# LCD_PWR.net
KiCad netlist of a schematic drawn in Altium Designer
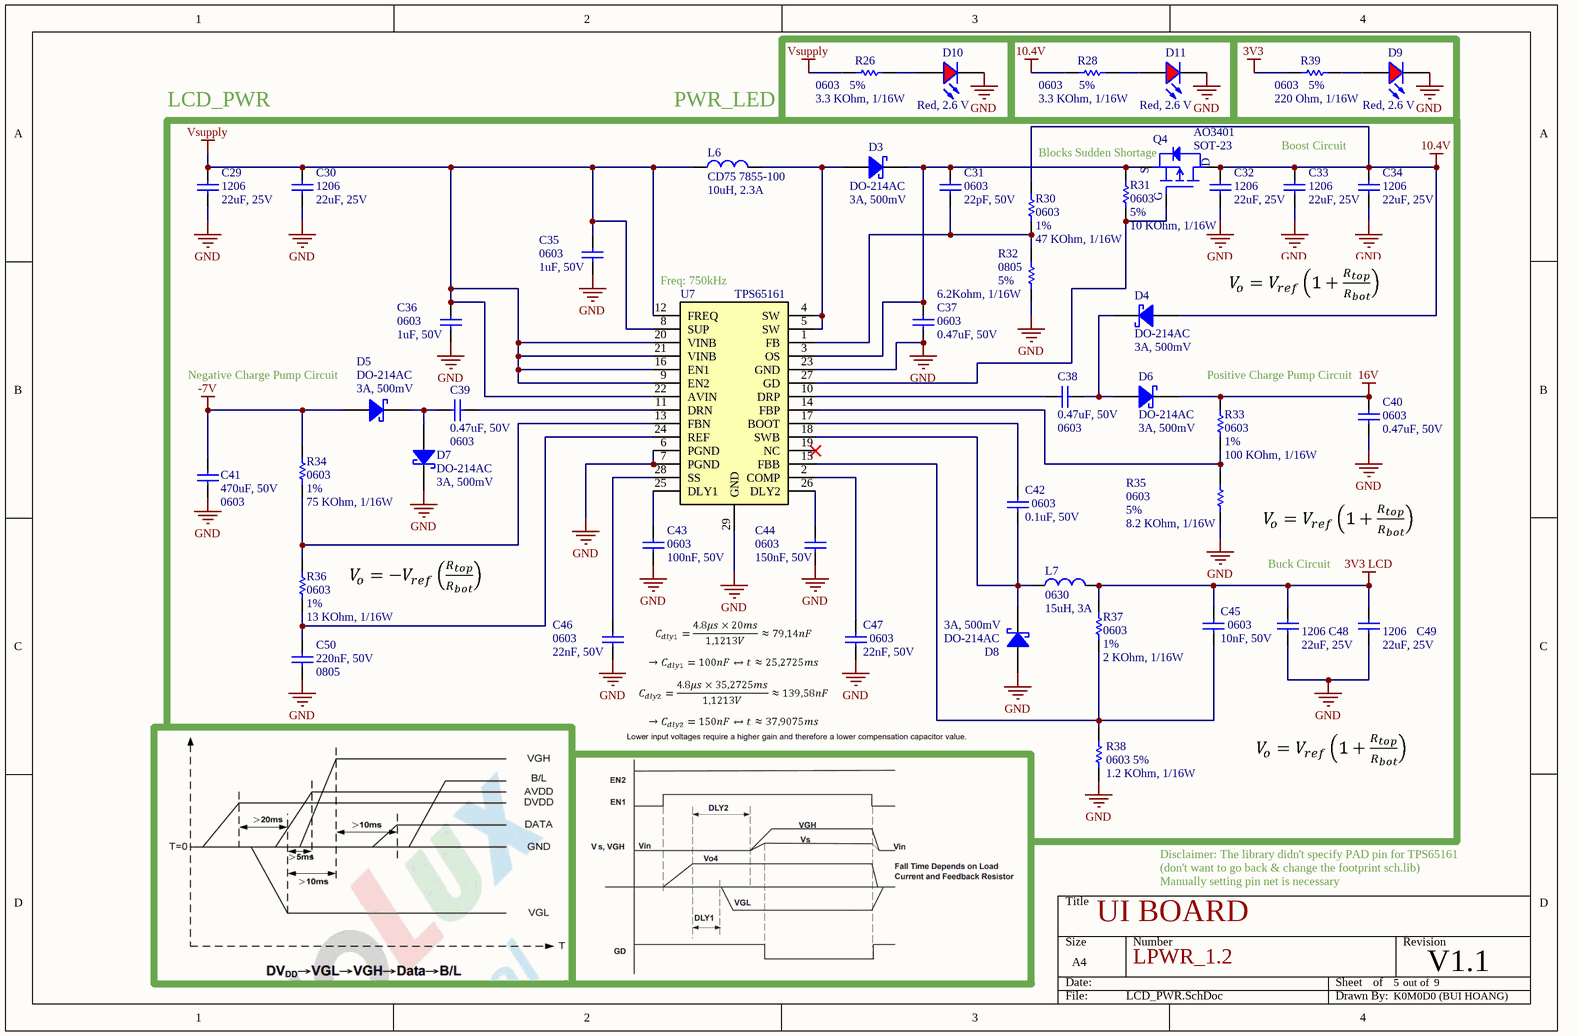
[diagram p0: LCD_PWR.SchDoc]

(export (version "E")
  (design (tool "Eeschema 10.0.6"))
  (components
    (comp (ref "C29")
      (value "22uF, 25V")
      (footprint "C_1206")
      (description "CAP_1206")
      (fields (field (name "PACKAGE") "1206"))
      (libsource (lib "DisplayLib") (part "CAP_1206"))
    )
    (comp (ref "C30")
      (value "22uF, 25V")
      (footprint "C_1206")
      (description "CAP_1206")
      (fields (field (name "PACKAGE") "1206"))
      (libsource (lib "DisplayLib") (part "CAP_1206"))
    )
    (comp (ref "C31")
      (value "22pF, 50V")
      (footprint "C_0603")
      (description "CAP_0603")
      (fields (field (name "PACKAGE") "0603"))
      (libsource (lib "DisplayLib") (part "CAP_0603"))
    )
    (comp (ref "C32")
      (value "22uF, 25V")
      (footprint "C_1206")
      (description "CAP_1206")
      (fields (field (name "PACKAGE") "1206"))
      (libsource (lib "DisplayLib") (part "CAP_1206"))
    )
    (comp (ref "C33")
      (value "22uF, 25V")
      (footprint "C_1206")
      (description "CAP_1206")
      (fields (field (name "PACKAGE") "1206"))
      (libsource (lib "DisplayLib") (part "CAP_1206"))
    )
    (comp (ref "C34")
      (value "22uF, 25V")
      (footprint "C_1206")
      (description "CAP_1206")
      (fields (field (name "PACKAGE") "1206"))
      (libsource (lib "DisplayLib") (part "CAP_1206"))
    )
    (comp (ref "C35")
      (value "1uF, 50V")
      (footprint "C_0603")
      (description "CAP_0603")
      (fields (field (name "PACKAGE") "0603"))
      (libsource (lib "DisplayLib") (part "CAP_0603"))
    )
    (comp (ref "C36")
      (value "1uF, 50V")
      (footprint "C_0603")
      (description "CAP_0603")
      (fields (field (name "PACKAGE") "0603"))
      (libsource (lib "DisplayLib") (part "CAP_0603"))
    )
    (comp (ref "C37")
      (value "0.47uF, 50V")
      (footprint "C_0603")
      (description "CAP_0603")
      (fields (field (name "PACKAGE") "0603"))
      (libsource (lib "DisplayLib") (part "CAP_0603"))
    )
    (comp (ref "C38")
      (value "0.47uF, 50V")
      (footprint "C_0603")
      (description "CAP_0603")
      (fields (field (name "PACKAGE") "0603"))
      (libsource (lib "DisplayLib") (part "CAP_0603"))
    )
    (comp (ref "C39")
      (value "0.47uF, 50V")
      (footprint "C_0603")
      (description "CAP_0603")
      (fields (field (name "PACKAGE") "0603"))
      (libsource (lib "DisplayLib") (part "CAP_0603"))
    )
    (comp (ref "C40")
      (value "0.47uF, 50V")
      (footprint "C_0603")
      (description "CAP_0603")
      (fields (field (name "PACKAGE") "0603"))
      (libsource (lib "DisplayLib") (part "CAP_0603"))
    )
    (comp (ref "C41")
      (value "470uF, 50V")
      (footprint "C_0603")
      (description "CAP_0603")
      (fields (field (name "PACKAGE") "0603"))
      (libsource (lib "DisplayLib") (part "CAP_0603"))
    )
    (comp (ref "C42")
      (value "0.1uF, 50V")
      (footprint "C_0603")
      (description "CAP_0603")
      (fields (field (name "PACKAGE") "0603"))
      (libsource (lib "DisplayLib") (part "CAP_0603"))
    )
    (comp (ref "C43")
      (value "100nF, 50V")
      (footprint "C_0603")
      (description "CAP_0603")
      (fields (field (name "PACKAGE") "0603"))
      (libsource (lib "DisplayLib") (part "CAP_0603"))
    )
    (comp (ref "C44")
      (value "150nF, 50V")
      (footprint "C_0603")
      (description "CAP_0603")
      (fields (field (name "PACKAGE") "0603"))
      (libsource (lib "DisplayLib") (part "CAP_0603"))
    )
    (comp (ref "C45")
      (value "10nF, 50V")
      (footprint "C_0603")
      (description "CAP_0603")
      (fields (field (name "PACKAGE") "0603"))
      (libsource (lib "DisplayLib") (part "CAP_0603"))
    )
    (comp (ref "C46")
      (value "22nF, 50V")
      (footprint "C_0603")
      (description "CAP_0603")
      (fields (field (name "PACKAGE") "0603"))
      (libsource (lib "DisplayLib") (part "CAP_0603"))
    )
    (comp (ref "C47")
      (value "22nF, 50V")
      (footprint "C_0603")
      (description "CAP_0603")
      (fields (field (name "PACKAGE") "0603"))
      (libsource (lib "DisplayLib") (part "CAP_0603"))
    )
    (comp (ref "C48")
      (value "22uF, 25V")
      (footprint "C_1206")
      (description "CAP_1206")
      (fields (field (name "PACKAGE") "1206"))
      (libsource (lib "DisplayLib") (part "CAP_1206"))
    )
    (comp (ref "C49")
      (value "22uF, 25V")
      (footprint "C_1206")
      (description "CAP_1206")
      (fields (field (name "PACKAGE") "1206"))
      (libsource (lib "DisplayLib") (part "CAP_1206"))
    )
    (comp (ref "C50")
      (value "220nF, 50V")
      (footprint "C_0805")
      (description "CAP_0805")
      (fields (field (name "PACKAGE") "0805"))
      (libsource (lib "DisplayLib") (part "CAP_0805"))
    )
    (comp (ref "D3")
      (value "3A, 500mV")
      (footprint "PKG_SMA (DO-214AC)")
      (description "SS34")
      (fields (field (name "PACKAGE") "DO-214AC"))
      (libsource (lib "DisplayLib") (part "SCHOTTKY"))
    )
    (comp (ref "D4")
      (value "3A, 500mV")
      (footprint "PKG_SMA (DO-214AC)")
      (description "SS34")
      (fields (field (name "PACKAGE") "DO-214AC"))
      (libsource (lib "DisplayLib") (part "SCHOTTKY"))
    )
    (comp (ref "D5")
      (value "3A, 500mV")
      (footprint "PKG_SMA (DO-214AC)")
      (description "SS34")
      (fields (field (name "PACKAGE") "DO-214AC"))
      (libsource (lib "DisplayLib") (part "SCHOTTKY"))
    )
    (comp (ref "D6")
      (value "3A, 500mV")
      (footprint "PKG_SMA (DO-214AC)")
      (description "SS34")
      (fields (field (name "PACKAGE") "DO-214AC"))
      (libsource (lib "DisplayLib") (part "SCHOTTKY"))
    )
    (comp (ref "D7")
      (value "3A, 500mV")
      (footprint "PKG_SMA (DO-214AC)")
      (description "SS34")
      (fields (field (name "PACKAGE") "DO-214AC"))
      (libsource (lib "DisplayLib") (part "SCHOTTKY"))
    )
    (comp (ref "D8")
      (value "3A, 500mV")
      (footprint "PKG_SMA (DO-214AC)")
      (description "SS34")
      (fields (field (name "PACKAGE") "DO-214AC"))
      (libsource (lib "DisplayLib") (part "SCHOTTKY"))
    )
    (comp (ref "D9")
      (value "Red, 2.6 V")
      (footprint "LED_1206")
      (description "Red LED")
      (libsource (lib "DisplayLib") (part "RED"))
    )
    (comp (ref "D10")
      (value "Red, 2.6 V")
      (footprint "LED_1206")
      (description "Red LED")
      (libsource (lib "DisplayLib") (part "RED"))
    )
    (comp (ref "D11")
      (value "Red, 2.6 V")
      (footprint "LED_1206")
      (description "Red LED")
      (libsource (lib "DisplayLib") (part "RED"))
    )
    (comp (ref "L6")
      (value "10uH, 2.3A")
      (footprint "COIL_CDRH")
      (description "IN_CD104_100")
      (fields (field (name "PACKAGE") "CD75 7855-100"))
      (libsource (lib "DisplayLib") (part "IN_CD104_100"))
    )
    (comp (ref "L7")
      (value "15uH, 3A")
      (footprint "COIL_74")
      (description "IN_0630")
      (fields (field (name "PACKAGE") "0630"))
      (libsource (lib "DisplayLib") (part "IN_0630"))
    )
    (comp (ref "Q4")
      (value "AO3401")
      (footprint "PKG_SOT-23")
      (description "P-Channel 30 V 4A (Ta) 1.4W (Ta) Surface Mount SOT-23-3")
      (fields (field (name "PACKAGE") "SOT-23"))
      (libsource (lib "DisplayLib") (part "AO3401"))
    )
    (comp (ref "R26")
      (value "3.3 KOhm, 1/16W")
      (footprint "R_0603")
      (description "RES_0603")
      (fields (field (name "PACKAGE") "0603") (field (name "ACC") "5%"))
      (libsource (lib "DisplayLib") (part "RES_0603"))
    )
    (comp (ref "R28")
      (value "3.3 KOhm, 1/16W")
      (footprint "R_0603")
      (description "RES_0603")
      (fields (field (name "PACKAGE") "0603") (field (name "ACC") "5%"))
      (libsource (lib "DisplayLib") (part "RES_0603"))
    )
    (comp (ref "R30")
      (value "47 KOhm, 1/16W")
      (footprint "R_0603")
      (description "RES_0603")
      (fields (field (name "PACKAGE") "0603") (field (name "ACC") "1%"))
      (libsource (lib "DisplayLib") (part "RES_0603"))
    )
    (comp (ref "R31")
      (value "10 KOhm, 1/16W")
      (footprint "R_0603")
      (description "RES_0603")
      (fields (field (name "PACKAGE") "0603") (field (name "ACC") "5%"))
      (libsource (lib "DisplayLib") (part "RES_0603"))
    )
    (comp (ref "R32")
      (value "6.2Kohm, 1/16W")
      (footprint "R_0805")
      (description "RES_0805")
      (fields (field (name "PACKAGE") "0805") (field (name "ACC") "5%"))
      (libsource (lib "DisplayLib") (part "RES_0805"))
    )
    (comp (ref "R33")
      (value "100 KOhm, 1/16W")
      (footprint "R_0603")
      (description "RES_0603")
      (fields (field (name "PACKAGE") "0603") (field (name "ACC") "1%"))
      (libsource (lib "DisplayLib") (part "RES_0603"))
    )
    (comp (ref "R34")
      (value "75 KOhm, 1/16W")
      (footprint "R_0603")
      (description "RES_0603")
      (fields (field (name "PACKAGE") "0603") (field (name "ACC") "1%"))
      (libsource (lib "DisplayLib") (part "RES_0603"))
    )
    (comp (ref "R35")
      (value "8.2 KOhm, 1/16W")
      (footprint "R_0603")
      (description "RES_0603")
      (fields (field (name "PACKAGE") "0603") (field (name "ACC") "5%"))
      (libsource (lib "DisplayLib") (part "RES_0603"))
    )
    (comp (ref "R36")
      (value "13 KOhm, 1/16W")
      (footprint "R_0603")
      (description "RES_0603")
      (fields (field (name "PACKAGE") "0603") (field (name "ACC") "1%"))
      (libsource (lib "DisplayLib") (part "RES_0603"))
    )
    (comp (ref "R37")
      (value "2 KOhm, 1/16W")
      (footprint "R_0603")
      (description "RES_0603")
      (fields (field (name "PACKAGE") "0603") (field (name "ACC") "1%"))
      (libsource (lib "DisplayLib") (part "RES_0603"))
    )
    (comp (ref "R38")
      (value "1.2 KOhm, 1/16W")
      (footprint "R_0603")
      (description "RES_0603")
      (fields (field (name "PACKAGE") "0603") (field (name "ACC") "5%"))
      (libsource (lib "DisplayLib") (part "RES_0603"))
    )
    (comp (ref "R39")
      (value "220 Ohm, 1/16W")
      (footprint "R_0603")
      (description "RES_0603")
      (fields (field (name "PACKAGE") "0603") (field (name "ACC") "5%"))
      (libsource (lib "DisplayLib") (part "RES_0603"))
    )
    (comp (ref "U7")
      (value "TPS65161")
      (footprint "PKG_HTSSOP-28")
      (description "BIAS POWER SUPPLY FOR TV AND MONITOR TFT LCD PANELS")
      (libsource (lib "DisplayLib") (part "TPS65161"))
    )
  )
  (nets
    (net (code "1") (name "-7V") (class "Default")
      (node (ref "C41") (pin "1") (pinfunction "1_1") (pintype "passive"))
      (node (ref "D5") (pin "2") (pinfunction "A_2") (pintype "passive"))
      (node (ref "R34") (pin "2") (pinfunction "2_2") (pintype "passive"))
    )
    (net (code "2") (name "3V3") (class "Default")
      (node (ref "R39") (pin "1") (pinfunction "1_1") (pintype "passive"))
    )
    (net (code "3") (name "3V3 LCD") (class "Default")
      (node (ref "C45") (pin "2") (pinfunction "2_2") (pintype "passive"))
      (node (ref "C48") (pin "2") (pinfunction "2_2") (pintype "passive"))
      (node (ref "C49") (pin "2") (pinfunction "2_2") (pintype "passive"))
      (node (ref "L7") (pin "2") (pinfunction "2_2") (pintype "passive"))
      (node (ref "R37") (pin "2") (pinfunction "2_2") (pintype "passive"))
    )
    (net (code "4") (name "10.4V") (class "Default")
      (node (ref "C32") (pin "2") (pinfunction "2_2") (pintype "passive"))
      (node (ref "C33") (pin "2") (pinfunction "2_2") (pintype "passive"))
      (node (ref "C34") (pin "2") (pinfunction "2_2") (pintype "passive"))
      (node (ref "D4") (pin "2") (pinfunction "A_2") (pintype "passive"))
      (node (ref "Q4") (pin "3") (pinfunction "D_3") (pintype "passive"))
      (node (ref "R28") (pin "1") (pinfunction "1_1") (pintype "passive"))
      (node (ref "R30") (pin "2") (pinfunction "2_2") (pintype "passive"))
    )
    (net (code "5") (name "16V") (class "Default")
      (node (ref "C40") (pin "2") (pinfunction "2_2") (pintype "passive"))
      (node (ref "D6") (pin "1") (pinfunction "K_1") (pintype "passive"))
      (node (ref "R33") (pin "2") (pinfunction "2_2") (pintype "passive"))
    )
    (net (code "6") (name "GND") (class "Default")
      (node (ref "C29") (pin "1") (pinfunction "1_1") (pintype "passive"))
      (node (ref "C30") (pin "1") (pinfunction "1_1") (pintype "passive"))
      (node (ref "C32") (pin "1") (pinfunction "1_1") (pintype "passive"))
      (node (ref "C33") (pin "1") (pinfunction "1_1") (pintype "passive"))
      (node (ref "C34") (pin "1") (pinfunction "1_1") (pintype "passive"))
      (node (ref "C35") (pin "1") (pinfunction "1_1") (pintype "passive"))
      (node (ref "C36") (pin "1") (pinfunction "1_1") (pintype "passive"))
      (node (ref "C37") (pin "1") (pinfunction "1_1") (pintype "passive"))
      (node (ref "C40") (pin "1") (pinfunction "1_1") (pintype "passive"))
      (node (ref "C41") (pin "2") (pinfunction "2_2") (pintype "passive"))
      (node (ref "C43") (pin "1") (pinfunction "1_1") (pintype "passive"))
      (node (ref "C44") (pin "1") (pinfunction "1_1") (pintype "passive"))
      (node (ref "C46") (pin "1") (pinfunction "1_1") (pintype "passive"))
      (node (ref "C47") (pin "1") (pinfunction "1_1") (pintype "passive"))
      (node (ref "C48") (pin "1") (pinfunction "1_1") (pintype "passive"))
      (node (ref "C49") (pin "1") (pinfunction "1_1") (pintype "passive"))
      (node (ref "C50") (pin "2") (pinfunction "2_2") (pintype "passive"))
      (node (ref "D10") (pin "1") (pinfunction "K_1") (pintype "passive"))
      (node (ref "D11") (pin "1") (pinfunction "K_1") (pintype "passive"))
      (node (ref "D7") (pin "1") (pinfunction "K_1") (pintype "passive"))
      (node (ref "D8") (pin "2") (pinfunction "A_2") (pintype "passive"))
      (node (ref "D9") (pin "1") (pinfunction "K_1") (pintype "passive"))
      (node (ref "R32") (pin "1") (pinfunction "1_1") (pintype "passive"))
      (node (ref "R35") (pin "1") (pinfunction "1_1") (pintype "passive"))
      (node (ref "R38") (pin "1") (pinfunction "1_1") (pintype "passive"))
      (node (ref "U7") (pin "23") (pinfunction "GND_23") (pintype "passive"))
      (node (ref "U7") (pin "29") (pinfunction "GND_29") (pintype "power_in"))
      (node (ref "U7") (pin "6") (pinfunction "PGND_6") (pintype "passive"))
      (node (ref "U7") (pin "7") (pinfunction "PGND_7") (pintype "passive"))
    )
    (net (code "7") (name "Net-(D3-A)") (class "Default")
      (node (ref "D3") (pin "2") (pinfunction "A_2") (pintype "passive"))
      (node (ref "L6") (pin "2") (pinfunction "2_2") (pintype "passive"))
      (node (ref "U7") (pin "4") (pinfunction "SW_4") (pintype "passive"))
      (node (ref "U7") (pin "5") (pinfunction "SW_5") (pintype "passive"))
    )
    (net (code "8") (name "Net-(D3-K)") (class "Default")
      (node (ref "C31") (pin "2") (pinfunction "2_2") (pintype "passive"))
      (node (ref "C37") (pin "2") (pinfunction "2_2") (pintype "passive"))
      (node (ref "D3") (pin "1") (pinfunction "K_1") (pintype "passive"))
      (node (ref "Q4") (pin "2") (pinfunction "S_2") (pintype "passive"))
      (node (ref "R31") (pin "2") (pinfunction "2_2") (pintype "passive"))
      (node (ref "U7") (pin "3") (pinfunction "OS_3") (pintype "passive"))
    )
    (net (code "9") (name "Net-(D4-K)") (class "Default")
      (node (ref "C38") (pin "1") (pinfunction "1_1") (pintype "passive"))
      (node (ref "D4") (pin "1") (pinfunction "K_1") (pintype "passive"))
      (node (ref "D6") (pin "2") (pinfunction "A_2") (pintype "passive"))
    )
    (net (code "10") (name "Net-(D5-K)") (class "Default")
      (node (ref "C39") (pin "2") (pinfunction "2_2") (pintype "passive"))
      (node (ref "D5") (pin "1") (pinfunction "K_1") (pintype "passive"))
      (node (ref "D7") (pin "2") (pinfunction "A_2") (pintype "passive"))
    )
    (net (code "11") (name "Net-(D8-K)") (class "Default")
      (node (ref "C42") (pin "1") (pinfunction "1_1") (pintype "passive"))
      (node (ref "D8") (pin "1") (pinfunction "K_1") (pintype "passive"))
      (node (ref "L7") (pin "1") (pinfunction "1_1") (pintype "passive"))
      (node (ref "U7") (pin "18") (pinfunction "SWB_18") (pintype "passive"))
    )
    (net (code "12") (name "Net-(D9-A)") (class "Default")
      (node (ref "D9") (pin "2") (pinfunction "A_2") (pintype "passive"))
      (node (ref "R39") (pin "2") (pinfunction "2_2") (pintype "passive"))
    )
    (net (code "13") (name "Net-(D10-A)") (class "Default")
      (node (ref "D10") (pin "2") (pinfunction "A_2") (pintype "passive"))
      (node (ref "R26") (pin "2") (pinfunction "2_2") (pintype "passive"))
    )
    (net (code "14") (name "Net-(D11-A)") (class "Default")
      (node (ref "D11") (pin "2") (pinfunction "A_2") (pintype "passive"))
      (node (ref "R28") (pin "2") (pinfunction "2_2") (pintype "passive"))
    )
    (net (code "15") (name "Net-(Q4-G)") (class "Default")
      (node (ref "Q4") (pin "1") (pinfunction "G_1") (pintype "passive"))
      (node (ref "R31") (pin "1") (pinfunction "1_1") (pintype "passive"))
      (node (ref "U7") (pin "27") (pinfunction "GD_27") (pintype "passive"))
    )
    (net (code "16") (name "Net-(U7-BOOT)") (class "Default")
      (node (ref "C42") (pin "2") (pinfunction "2_2") (pintype "passive"))
      (node (ref "U7") (pin "17") (pinfunction "BOOT_17") (pintype "passive"))
    )
    (net (code "17") (name "Net-(U7-COMP)") (class "Default")
      (node (ref "C47") (pin "2") (pinfunction "2_2") (pintype "passive"))
      (node (ref "U7") (pin "2") (pinfunction "COMP_2") (pintype "passive"))
    )
    (net (code "18") (name "Net-(U7-DLY1)") (class "Default")
      (node (ref "C43") (pin "2") (pinfunction "2_2") (pintype "passive"))
      (node (ref "U7") (pin "25") (pinfunction "DLY1_25") (pintype "passive"))
    )
    (net (code "19") (name "Net-(U7-DLY2)") (class "Default")
      (node (ref "C44") (pin "2") (pinfunction "2_2") (pintype "passive"))
      (node (ref "U7") (pin "26") (pinfunction "DLY2_26") (pintype "passive"))
    )
    (net (code "20") (name "Net-(U7-DRN)") (class "Default")
      (node (ref "C39") (pin "1") (pinfunction "1_1") (pintype "passive"))
      (node (ref "U7") (pin "11") (pinfunction "DRN_11") (pintype "passive"))
    )
    (net (code "21") (name "Net-(U7-DRP)") (class "Default")
      (node (ref "C38") (pin "2") (pinfunction "2_2") (pintype "passive"))
      (node (ref "U7") (pin "10") (pinfunction "DRP_10") (pintype "passive"))
    )
    (net (code "22") (name "Net-(U7-FB)") (class "Default")
      (node (ref "C31") (pin "1") (pinfunction "1_1") (pintype "passive"))
      (node (ref "R30") (pin "1") (pinfunction "1_1") (pintype "passive"))
      (node (ref "R32") (pin "2") (pinfunction "2_2") (pintype "passive"))
      (node (ref "U7") (pin "1") (pinfunction "FB_1") (pintype "passive"))
    )
    (net (code "23") (name "Net-(U7-FBB)") (class "Default")
      (node (ref "C45") (pin "1") (pinfunction "1_1") (pintype "passive"))
      (node (ref "R37") (pin "1") (pinfunction "1_1") (pintype "passive"))
      (node (ref "R38") (pin "2") (pinfunction "2_2") (pintype "passive"))
      (node (ref "U7") (pin "15") (pinfunction "FBB_15") (pintype "passive"))
    )
    (net (code "24") (name "Net-(U7-FBN)") (class "Default")
      (node (ref "R34") (pin "1") (pinfunction "1_1") (pintype "passive"))
      (node (ref "R36") (pin "2") (pinfunction "2_2") (pintype "passive"))
      (node (ref "U7") (pin "13") (pinfunction "FBN_13") (pintype "passive"))
    )
    (net (code "25") (name "Net-(U7-FBP)") (class "Default")
      (node (ref "R33") (pin "1") (pinfunction "1_1") (pintype "passive"))
      (node (ref "R35") (pin "2") (pinfunction "2_2") (pintype "passive"))
      (node (ref "U7") (pin "14") (pinfunction "FBP_14") (pintype "passive"))
    )
    (net (code "26") (name "Net-(U7-REF)") (class "Default")
      (node (ref "C50") (pin "1") (pinfunction "1_1") (pintype "passive"))
      (node (ref "R36") (pin "1") (pinfunction "1_1") (pintype "passive"))
      (node (ref "U7") (pin "24") (pinfunction "REF_24") (pintype "passive"))
    )
    (net (code "27") (name "Net-(U7-SS)") (class "Default")
      (node (ref "C46") (pin "2") (pinfunction "2_2") (pintype "passive"))
      (node (ref "U7") (pin "28") (pinfunction "SS_28") (pintype "passive"))
    )
    (net (code "28") (name "Vsupply") (class "Default")
      (node (ref "C29") (pin "2") (pinfunction "2_2") (pintype "passive"))
      (node (ref "C30") (pin "2") (pinfunction "2_2") (pintype "passive"))
      (node (ref "C35") (pin "2") (pinfunction "2_2") (pintype "passive"))
      (node (ref "C36") (pin "2") (pinfunction "2_2") (pintype "passive"))
      (node (ref "L6") (pin "1") (pinfunction "1_1") (pintype "passive"))
      (node (ref "R26") (pin "1") (pinfunction "1_1") (pintype "passive"))
      (node (ref "U7") (pin "12") (pinfunction "FREQ_12") (pintype "passive"))
      (node (ref "U7") (pin "16") (pinfunction "EN1_16") (pintype "passive"))
      (node (ref "U7") (pin "20") (pinfunction "VINB_20") (pintype "passive"))
      (node (ref "U7") (pin "21") (pinfunction "VINB_21") (pintype "passive"))
      (node (ref "U7") (pin "22") (pinfunction "AVIN_22") (pintype "passive"))
      (node (ref "U7") (pin "8") (pinfunction "SUP_8") (pintype "passive"))
      (node (ref "U7") (pin "9") (pinfunction "EN2_9") (pintype "passive"))
    )
    (net (code "29") (name "unconnected-(U7-NC-Pad19)") (class "Default")
      (node (ref "U7") (pin "19") (pinfunction "NC_19") (pintype "passive+no_connect"))
    )
  )
)
